# CAN_Bus.net
KiCad netlist of a schematic drawn in Altium Designer
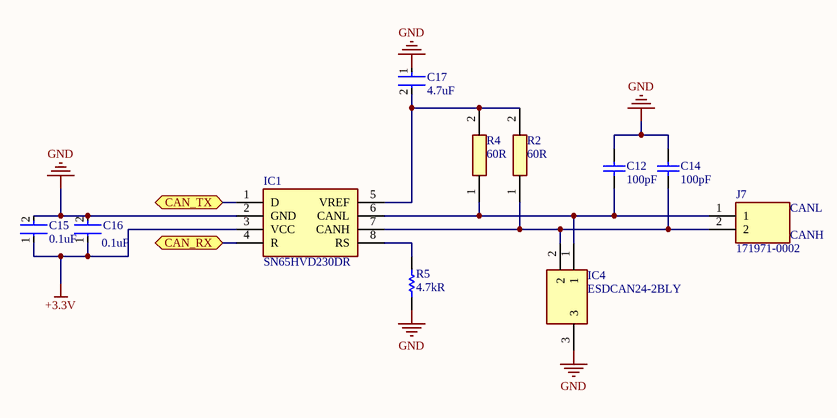
[diagram p0: CAN Bus.SchDoc]

(export (version "E")
  (design (tool "Eeschema 10.0.6"))
  (components
    (comp (ref "C12")
      (value "100pF")
      (footprint "CAPC1608X90X35NL10T15")
      (fields (field (name "PART NUMBER") "GRM1885C1H101JA01D") (field (name "MANUFACTURER") "Murata"))
      (libsource (lib "Altium Content Vault") (part "CAP"))
    )
    (comp (ref "C14")
      (value "100pF")
      (footprint "CAPC1608X90X35NL10T15")
      (fields (field (name "PART NUMBER") "GRM1885C1H101JA01D") (field (name "MANUFACTURER") "Murata"))
      (libsource (lib "Altium Content Vault") (part "CAP"))
    )
    (comp (ref "C15")
      (value "0.1uF")
      (footprint "FP-GRM15-MFG")
      (description "CAP CER 0.1UF 16V X7R 0402")
      (fields (field (name "MANUFACTURER PART NUMBER") "GRM155R71C104KA88D") (field (name "TOLERANCE") "10%"))
      (libsource (lib "Altium Content Vault") (part "236180d848d6139a670b325ea6854c9"))
    )
    (comp (ref "C16")
      (value "0.1uF")
      (footprint "FP-GRM15-MFG")
      (description "CAP CER 0.1UF 16V X7R 0402")
      (fields (field (name "MANUFACTURER PART NUMBER") "GRM155R71C104KA88D") (field (name "TOLERANCE") "10%"))
      (libsource (lib "Altium Content Vault") (part "236180d848d6139a670b325ea6854c9"))
    )
    (comp (ref "C17")
      (value "4.7uF")
      (footprint "FP-GRM155-0_1-IPC_B")
      (description "Chip Multilayer Ceramic Capacitors for General Purpose, 0402, 4.7uF, X5R, 15%, 20%, 6.3V")
      (fields (field (name "VOLTAGE") "6.3V") (field (name "TOLERANCE") "20%"))
      (libsource (lib "Altium Content Vault") (part "11868f565c42a9108669ba33697ecf6"))
    )
    (comp (ref "IC1")
      (value "SN65HVD230DR")
      (footprint "SamacSys:SOT127P600X175-8N")
      (description "Integrated Circuit")
      (fields (field (name "MOUSER2 PART NUMBER") "595-SN65HVD230DR"))
      (libsource (lib "SamacSys") (part "SN65HVD230DR"))
    )
    (comp (ref "IC4")
      (value "ESDCAN24-2BLY")
      (footprint "SamacSys:SOT105P255X150-3N")
      (description "Integrated Circuit")
      (fields (field (name "MOUSER2 PART NUMBER") "511-ESDCAN24-2BLY"))
      (libsource (lib "SamacSys") (part "ESDCAN24-2BLY"))
    )
    (comp (ref "J7")
      (value "171971-0002")
      (footprint "SamacSys:SHDR2W65P0X254_1X2_738X510X1216P")
      (description "Connector")
      (fields (field (name "MOUSER2 PART NUMBER") "538-171971-0002"))
      (libsource (lib "SamacSys") (part "171971-0002"))
    )
    (comp (ref "R2")
      (value "60R")
      (footprint "SamacSys:RESC3216X60N")
      (description "Resistor")
      (fields (field (name "MANUFACTURER_PART_NUMBER") "CRCW120660R0KNEAIF"))
      (libsource (lib "SamacSys") (part "CRCW120660R0KNEAIF"))
    )
    (comp (ref "R4")
      (value "60R")
      (footprint "SamacSys:RESC3216X60N")
      (description "Resistor")
      (fields (field (name "MANUFACTURER_PART_NUMBER") "CRCW120660R0KNEAIF"))
      (libsource (lib "SamacSys") (part "CRCW120660R0KNEAIF"))
    )
    (comp (ref "R5")
      (value "4.7kR")
      (footprint "RESC3216X60X45ML15T20")
      (description "Chip Resistor, 4.7 KOhm, +/- 1%, 0.25 W, -55 to 155 degC, 1206 (3216 Metric), RoHS, Tape and Reel")
      (fields (field (name "MANUFACTURER") "Vishay Semiconductor") (field (name "TOLERANCE") "1%"))
      (libsource (lib "Altium Content Vault") (part "RES-2"))
    )
  )
  (nets
    (net (code "1") (name "+3.3V") (class "Default")
      (node (ref "C15") (pin "1") (pinfunction "1_1") (pintype "passive"))
      (node (ref "C16") (pin "1") (pinfunction "1_1") (pintype "passive"))
      (node (ref "IC1") (pin "3") (pinfunction "VCC_3") (pintype "passive"))
    )
    (net (code "2") (name "/CAN_RX") (class "Default")
      (node (ref "IC1") (pin "4") (pinfunction "R_4") (pintype "passive"))
    )
    (net (code "3") (name "/CAN_TX") (class "Default")
      (node (ref "IC1") (pin "1") (pinfunction "D_1") (pintype "passive"))
    )
    (net (code "4") (name "GND") (class "Default")
      (node (ref "C12") (pin "2") (pinfunction "2_2") (pintype "passive"))
      (node (ref "C14") (pin "2") (pinfunction "2_2") (pintype "passive"))
      (node (ref "C15") (pin "2") (pinfunction "2_2") (pintype "passive"))
      (node (ref "C16") (pin "2") (pinfunction "2_2") (pintype "passive"))
      (node (ref "C17") (pin "1") (pinfunction "1_1") (pintype "passive"))
      (node (ref "IC1") (pin "2") (pinfunction "GND_2") (pintype "passive"))
      (node (ref "IC4") (pin "3") (pinfunction "3_3") (pintype "passive"))
      (node (ref "R5") (pin "1") (pinfunction "1_1") (pintype "passive"))
    )
    (net (code "5") (name "Net-(IC1-CANH)") (class "Default")
      (node (ref "C14") (pin "1") (pinfunction "1_1") (pintype "passive"))
      (node (ref "IC1") (pin "7") (pinfunction "CANH_7") (pintype "passive"))
      (node (ref "IC4") (pin "2") (pinfunction "2_2") (pintype "passive"))
      (node (ref "J7") (pin "2") (pinfunction "2_2") (pintype "passive"))
      (node (ref "R2") (pin "1") (pinfunction "1_1") (pintype "passive"))
    )
    (net (code "6") (name "Net-(IC1-CANL)") (class "Default")
      (node (ref "C12") (pin "1") (pinfunction "1_1") (pintype "passive"))
      (node (ref "IC1") (pin "6") (pinfunction "CANL_6") (pintype "passive"))
      (node (ref "IC4") (pin "1") (pinfunction "1_1") (pintype "passive"))
      (node (ref "J7") (pin "1") (pinfunction "1_1") (pintype "passive"))
      (node (ref "R4") (pin "1") (pinfunction "1_1") (pintype "passive"))
    )
    (net (code "7") (name "Net-(IC1-RS)") (class "Default")
      (node (ref "IC1") (pin "8") (pinfunction "RS_8") (pintype "passive"))
      (node (ref "R5") (pin "2") (pinfunction "2_2") (pintype "passive"))
    )
    (net (code "8") (name "Net-(IC1-VREF)") (class "Default")
      (node (ref "C17") (pin "2") (pinfunction "2_2") (pintype "passive"))
      (node (ref "IC1") (pin "5") (pinfunction "VREF_5") (pintype "passive"))
      (node (ref "R2") (pin "2") (pinfunction "2_2") (pintype "passive"))
      (node (ref "R4") (pin "2") (pinfunction "2_2") (pintype "passive"))
    )
  )
)
